# Medium_switch_1.net
KiCad netlist of a schematic drawn in EAGLE
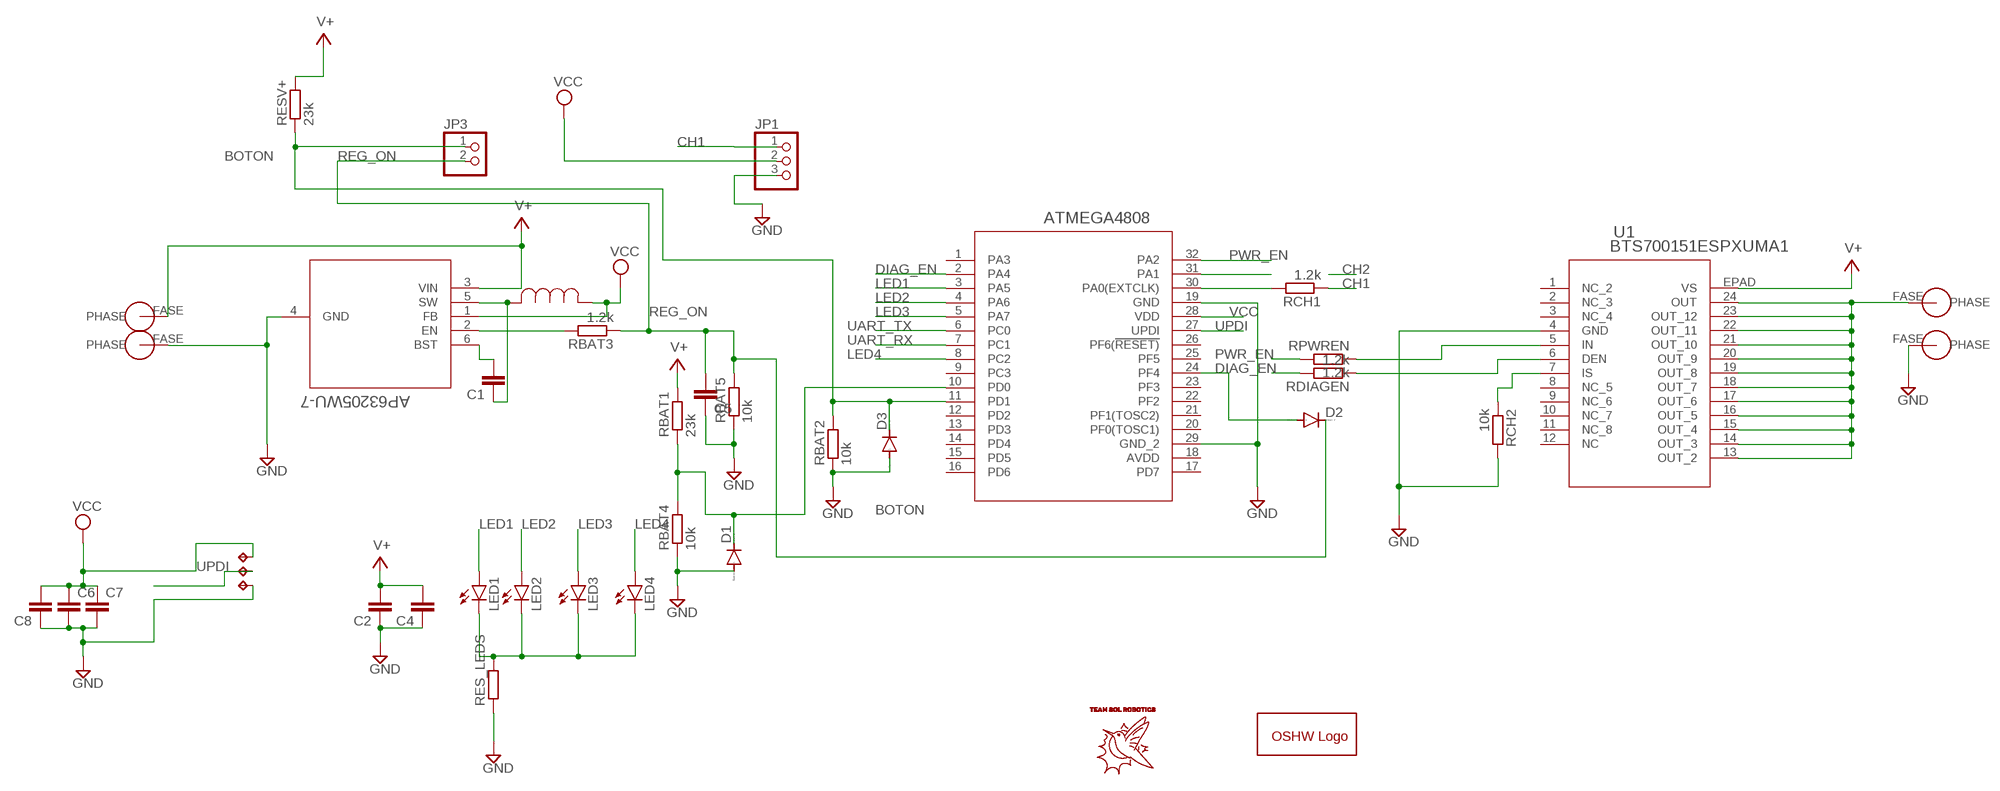
[diagram p0: schematic, sheet 1]

(export (version "E")
  (design (tool "Eeschema 10.0.6"))
  (components
    (comp (ref "BAT+")
      (value "PHASE")
      (footprint "eagle-import:POWEROUT")
      (libsource (lib "eagle-import") (part "PHASE"))
    )
    (comp (ref "C1")
      (value "C-EUC0402")
      (footprint "eagle-import:C0402")
      (libsource (lib "eagle-import") (part "C-EUC0402"))
    )
    (comp (ref "C2")
      (value "C-EUC1206")
      (footprint "eagle-import:C1206")
      (libsource (lib "eagle-import") (part "C-EUC1206"))
    )
    (comp (ref "C4")
      (value "C-EUC1206")
      (footprint "eagle-import:C1206")
      (libsource (lib "eagle-import") (part "C-EUC1206"))
    )
    (comp (ref "C5")
      (value "C-EUC0402")
      (footprint "eagle-import:C0402")
      (libsource (lib "eagle-import") (part "C-EUC0402"))
    )
    (comp (ref "C6")
      (value "C-EUC0805")
      (footprint "eagle-import:C0805")
      (libsource (lib "eagle-import") (part "C-EUC0805"))
    )
    (comp (ref "C7")
      (value "C-EUC0805")
      (footprint "eagle-import:C0805")
      (libsource (lib "eagle-import") (part "C-EUC0805"))
    )
    (comp (ref "C8")
      (value "C-EUC0402")
      (footprint "eagle-import:C0402")
      (libsource (lib "eagle-import") (part "C-EUC0402"))
    )
    (comp (ref "D1")
      (value "DIODE-MICROMELF-R")
      (footprint "eagle-import:MICROMELF-R")
      (libsource (lib "eagle-import") (part "DIODE-MICROMELF-R"))
    )
    (comp (ref "D2")
      (value "DIODE-MINIMELF")
      (footprint "eagle-import:MINIMELF")
      (libsource (lib "eagle-import") (part "DIODE-MINIMELF"))
    )
    (comp (ref "D3")
      (value "DIODE-MICROMELF-R")
      (footprint "eagle-import:MICROMELF-R")
      (libsource (lib "eagle-import") (part "DIODE-MICROMELF-R"))
    )
    (comp (ref "FASEA1")
      (value "PHASE")
      (footprint "eagle-import:POWEROUT")
      (libsource (lib "eagle-import") (part "PHASE"))
    )
    (comp (ref "FASEA3")
      (value "PHASE")
      (footprint "eagle-import:POWEROUT")
      (libsource (lib "eagle-import") (part "PHASE"))
    )
    (comp (ref "GOLD_ORB_SM1")
      (value "OSHWLOGOLOGO5MM")
      (footprint "eagle-import:OSHW_5MM")
      (libsource (lib "eagle-import") (part "OSHWLOGOLOGO5MM"))
    )
    (comp (ref "JP1")
      (value "PINHD-1X03_2.54-S")
      (footprint "eagle-import:1X03-S")
      (libsource (lib "eagle-import") (part "PINHD-1X03_2.54-S"))
    )
    (comp (ref "JP3")
      (value "PINHD-1X02_2.00")
      (footprint "eagle-import:1X02M")
      (libsource (lib "eagle-import") (part "PINHD-1X02_2.00"))
    )
    (comp (ref "LED1")
      (value "LEDSML0603")
      (footprint "eagle-import:SML0603")
      (libsource (lib "eagle-import") (part "LEDSML0603"))
    )
    (comp (ref "LED2")
      (value "LEDSML0603")
      (footprint "eagle-import:SML0603")
      (libsource (lib "eagle-import") (part "LEDSML0603"))
    )
    (comp (ref "LED3")
      (value "LEDSML0603")
      (footprint "eagle-import:SML0603")
      (libsource (lib "eagle-import") (part "LEDSML0603"))
    )
    (comp (ref "LED4")
      (value "LEDSML0603")
      (footprint "eagle-import:SML0603")
      (libsource (lib "eagle-import") (part "LEDSML0603"))
    )
    (comp (ref "OUTPUTPWR")
      (value "PHASE")
      (footprint "eagle-import:POWEROUT")
      (libsource (lib "eagle-import") (part "PHASE"))
    )
    (comp (ref "RBAT1")
      (value "23k")
      (footprint "eagle-import:R0603")
      (libsource (lib "eagle-import") (part "R-EU_R0603"))
    )
    (comp (ref "RBAT2")
      (value "10k")
      (footprint "eagle-import:R0603")
      (libsource (lib "eagle-import") (part "R-EU_R0603"))
    )
    (comp (ref "RBAT3")
      (value "1.2k")
      (footprint "eagle-import:R0603")
      (libsource (lib "eagle-import") (part "R-EU_R0603"))
    )
    (comp (ref "RBAT4")
      (value "10k")
      (footprint "eagle-import:R0603")
      (libsource (lib "eagle-import") (part "R-EU_R0603"))
    )
    (comp (ref "RBAT5")
      (value "10k")
      (footprint "eagle-import:R0603")
      (libsource (lib "eagle-import") (part "R-EU_R0603"))
    )
    (comp (ref "RCH1")
      (value "1.2k")
      (footprint "eagle-import:R0603")
      (libsource (lib "eagle-import") (part "R-EU_R0603"))
    )
    (comp (ref "RCH2")
      (value "10k")
      (footprint "eagle-import:R0603")
      (libsource (lib "eagle-import") (part "R-EU_R0603"))
    )
    (comp (ref "RDIAGEN")
      (value "1.2k")
      (footprint "eagle-import:R0603")
      (libsource (lib "eagle-import") (part "R-EU_R0603"))
    )
    (comp (ref "RESV+")
      (value "23k")
      (footprint "eagle-import:R0603")
      (libsource (lib "eagle-import") (part "R-EU_R0603"))
    )
    (comp (ref "RES_LEDS")
      (value "R-EU_R0603")
      (footprint "eagle-import:R0603")
      (libsource (lib "eagle-import") (part "R-EU_R0603"))
    )
    (comp (ref "RPWREN")
      (value "1.2k")
      (footprint "eagle-import:R0603")
      (libsource (lib "eagle-import") (part "R-EU_R0603"))
    )
    (comp (ref "TP1")
      (value "TPTP13SQ")
      (footprint "eagle-import:TP13SQ")
      (libsource (lib "eagle-import") (part "TPTP13SQ"))
    )
    (comp (ref "TP2")
      (value "TPTP13SQ")
      (footprint "eagle-import:TP13SQ")
      (libsource (lib "eagle-import") (part "TPTP13SQ"))
    )
    (comp (ref "TP3")
      (value "TPTP13SQ")
      (footprint "eagle-import:TP13SQ")
      (libsource (lib "eagle-import") (part "TPTP13SQ"))
    )
    (comp (ref "U$1")
      (value "ATMEGA4808")
      (footprint "eagle-import:QFP80P900X900X120-32N")
      (libsource (lib "eagle-import") (part "ATMEGA4808"))
    )
    (comp (ref "U$3")
      (value "INDUCTOR4.7")
      (footprint "eagle-import:IND_NRS5030T100MMGJ_TAY")
      (libsource (lib "eagle-import") (part "INDUCTOR4.7"))
    )
    (comp (ref "U1")
      (value "BTS700151ESPXUMA1")
      (footprint "eagle-import:PG-TSDSO-24-32")
      (fields (field (name "COPYRIGHT") "Copyright (C) 2023 Ultra Librarian. All rights reserved."))
      (libsource (lib "eagle-import") (part "BTS700151ESPXUMA1"))
    )
    (comp (ref "U2")
      (value "AP63205WU-7")
      (footprint "eagle-import:SOIC_05WU-7_DIO")
      (fields (field (name "COPYRIGHT") "Copyright (C) 2018 Accelerated Designs. All rights reserved"))
      (libsource (lib "eagle-import") (part "AP63205WU-7"))
    )
  )
  (nets
    (net (code "1") (name "/AVDD") (class "Default")
      (node (ref "U$1") (pin "18") (pinfunction "AVDD_18") (pintype "power_in"))
    )
    (net (code "2") (name "/BOTON") (class "Default")
      (node (ref "D3") (pin "C") (pinfunction "C_C") (pintype "passive"))
      (node (ref "JP3") (pin "1") (pinfunction "1_1") (pintype "passive"))
      (node (ref "RBAT2") (pin "2") (pinfunction "2_2") (pintype "passive"))
      (node (ref "RESV+") (pin "1") (pinfunction "1_1") (pintype "passive"))
      (node (ref "U$1") (pin "11") (pinfunction "PD1_11") (pintype "bidirectional"))
    )
    (net (code "3") (name "/CH1") (class "Default")
      (node (ref "JP1") (pin "1") (pinfunction "1_1") (pintype "passive"))
      (node (ref "RCH1") (pin "1") (pinfunction "1_1") (pintype "passive"))
    )
    (net (code "5") (name "/DIAG_EN") (class "Default")
      (node (ref "RDIAGEN") (pin "2") (pinfunction "2_2") (pintype "passive"))
      (node (ref "U$1") (pin "2") (pinfunction "PA4_2") (pintype "bidirectional"))
    )
    (net (code "6") (name "/LED1") (class "Default")
      (node (ref "LED1") (pin "A") (pinfunction "A_A") (pintype "passive"))
      (node (ref "U$1") (pin "3") (pinfunction "PA5_3") (pintype "bidirectional"))
    )
    (net (code "7") (name "/LED2") (class "Default")
      (node (ref "LED2") (pin "A") (pinfunction "A_A") (pintype "passive"))
      (node (ref "U$1") (pin "4") (pinfunction "PA6_4") (pintype "bidirectional"))
    )
    (net (code "8") (name "/LED3") (class "Default")
      (node (ref "LED3") (pin "A") (pinfunction "A_A") (pintype "passive"))
      (node (ref "U$1") (pin "5") (pinfunction "PA7_5") (pintype "bidirectional"))
    )
    (net (code "9") (name "/LED4") (class "Default")
      (node (ref "LED4") (pin "A") (pinfunction "A_A") (pintype "passive"))
      (node (ref "U$1") (pin "8") (pinfunction "PC2_8") (pintype "bidirectional"))
    )
    (net (code "10") (name "/PWR_EN") (class "Default")
      (node (ref "RPWREN") (pin "2") (pinfunction "2_2") (pintype "passive"))
      (node (ref "U$1") (pin "32") (pinfunction "PA2_32") (pintype "bidirectional"))
    )
    (net (code "11") (name "/REG_ON") (class "Default")
      (node (ref "C5") (pin "2") (pinfunction "2_2") (pintype "passive"))
      (node (ref "D2") (pin "C") (pinfunction "C_C") (pintype "passive"))
      (node (ref "JP3") (pin "2") (pinfunction "2_2") (pintype "passive"))
      (node (ref "RBAT3") (pin "1") (pinfunction "1_1") (pintype "passive"))
      (node (ref "RBAT5") (pin "2") (pinfunction "2_2") (pintype "passive"))
    )
    (net (code "12") (name "/UART_RX") (class "Default")
      (node (ref "U$1") (pin "7") (pinfunction "PC1_7") (pintype "bidirectional"))
    )
    (net (code "13") (name "/UART_TX") (class "Default")
      (node (ref "U$1") (pin "6") (pinfunction "PC0_6") (pintype "bidirectional"))
    )
    (net (code "14") (name "/UPDI") (class "Default")
      (node (ref "TP3") (pin "TP") (pinfunction "TP_TP") (pintype "input"))
      (node (ref "U$1") (pin "27") (pinfunction "UPDI_27") (pintype "bidirectional"))
    )
    (net (code "15") (name "GND") (class "Default")
      (node (ref "C2") (pin "1") (pinfunction "1_1") (pintype "passive"))
      (node (ref "C4") (pin "1") (pinfunction "1_1") (pintype "passive"))
      (node (ref "C5") (pin "1") (pinfunction "1_1") (pintype "passive"))
      (node (ref "C6") (pin "2") (pinfunction "2_2") (pintype "passive"))
      (node (ref "C7") (pin "2") (pinfunction "2_2") (pintype "passive"))
      (node (ref "C8") (pin "1") (pinfunction "1_1") (pintype "passive"))
      (node (ref "D1") (pin "A") (pinfunction "A_A") (pintype "passive"))
      (node (ref "D3") (pin "A") (pinfunction "A_A") (pintype "passive"))
      (node (ref "FASEA1") (pin "FASE") (pinfunction "PHASE_FASE") (pintype "bidirectional"))
      (node (ref "FASEA3") (pin "FASE") (pinfunction "PHASE_FASE") (pintype "bidirectional"))
      (node (ref "JP1") (pin "3") (pinfunction "3_3") (pintype "passive"))
      (node (ref "RBAT2") (pin "1") (pinfunction "1_1") (pintype "passive"))
      (node (ref "RBAT4") (pin "1") (pinfunction "1_1") (pintype "passive"))
      (node (ref "RBAT5") (pin "1") (pinfunction "1_1") (pintype "passive"))
      (node (ref "RCH2") (pin "2") (pinfunction "2_2") (pintype "passive"))
      (node (ref "RES_LEDS") (pin "1") (pinfunction "1_1") (pintype "passive"))
      (node (ref "TP2") (pin "TP") (pinfunction "TP_TP") (pintype "input"))
      (node (ref "U$1") (pin "19") (pinfunction "GND_19") (pintype "passive"))
      (node (ref "U$1") (pin "29") (pinfunction "GND_2_29") (pintype "passive"))
      (node (ref "U1") (pin "4") (pinfunction "GND_4") (pintype "passive"))
      (node (ref "U2") (pin "4") (pinfunction "GND_4") (pintype "passive"))
    )
    (net (code "16") (name "Net-(LED1-PadC)") (class "Default")
      (node (ref "LED1") (pin "C") (pinfunction "C_C") (pintype "passive"))
      (node (ref "LED2") (pin "C") (pinfunction "C_C") (pintype "passive"))
      (node (ref "LED3") (pin "C") (pinfunction "C_C") (pintype "passive"))
      (node (ref "LED4") (pin "C") (pinfunction "C_C") (pintype "passive"))
      (node (ref "RES_LEDS") (pin "2") (pinfunction "2_2") (pintype "passive"))
    )
    (net (code "17") (name "Net-(OUTPUTPWR-PHASE)") (class "Default")
      (node (ref "OUTPUTPWR") (pin "FASE") (pinfunction "PHASE_FASE") (pintype "bidirectional"))
      (node (ref "U1") (pin "13") (pinfunction "OUT_2_13") (pintype "output"))
      (node (ref "U1") (pin "14") (pinfunction "OUT_3_14") (pintype "output"))
      (node (ref "U1") (pin "15") (pinfunction "OUT_4_15") (pintype "output"))
      (node (ref "U1") (pin "16") (pinfunction "OUT_5_16") (pintype "output"))
      (node (ref "U1") (pin "17") (pinfunction "OUT_6_17") (pintype "output"))
      (node (ref "U1") (pin "18") (pinfunction "OUT_7_18") (pintype "output"))
      (node (ref "U1") (pin "19") (pinfunction "OUT_8_19") (pintype "output"))
      (node (ref "U1") (pin "20") (pinfunction "OUT_9_20") (pintype "output"))
      (node (ref "U1") (pin "21") (pinfunction "OUT_10_21") (pintype "output"))
      (node (ref "U1") (pin "22") (pinfunction "OUT_11_22") (pintype "output"))
      (node (ref "U1") (pin "23") (pinfunction "OUT_12_23") (pintype "output"))
      (node (ref "U1") (pin "24") (pinfunction "OUT_24") (pintype "output"))
    )
    (net (code "18") (name "Net-(U$1-PA0(EXTCLK))") (class "Default")
      (node (ref "RCH1") (pin "2") (pinfunction "2_2") (pintype "passive"))
      (node (ref "U$1") (pin "30") (pinfunction "PA0(EXTCLK)_30") (pintype "bidirectional"))
    )
    (net (code "19") (name "Net-(U$1-PD0)") (class "Default")
      (node (ref "D1") (pin "C") (pinfunction "C_C") (pintype "passive"))
      (node (ref "RBAT1") (pin "1") (pinfunction "1_1") (pintype "passive"))
      (node (ref "RBAT4") (pin "2") (pinfunction "2_2") (pintype "passive"))
      (node (ref "U$1") (pin "10") (pinfunction "PD0_10") (pintype "bidirectional"))
    )
    (net (code "20") (name "Net-(U$1-PF4)") (class "Default")
      (node (ref "D2") (pin "A") (pinfunction "A_A") (pintype "passive"))
      (node (ref "U$1") (pin "24") (pinfunction "PF4_24") (pintype "bidirectional"))
    )
    (net (code "21") (name "Net-(U1-DEN)") (class "Default")
      (node (ref "RDIAGEN") (pin "1") (pinfunction "1_1") (pintype "passive"))
      (node (ref "U1") (pin "6") (pinfunction "DEN_6") (pintype "passive"))
    )
    (net (code "22") (name "Net-(U1-IN)") (class "Default")
      (node (ref "RPWREN") (pin "1") (pinfunction "1_1") (pintype "passive"))
      (node (ref "U1") (pin "5") (pinfunction "IN_5") (pintype "input"))
    )
    (net (code "23") (name "Net-(U1-IS)") (class "Default")
      (node (ref "RCH2") (pin "1") (pinfunction "1_1") (pintype "passive"))
      (node (ref "U1") (pin "7") (pinfunction "IS_7") (pintype "passive"))
    )
    (net (code "24") (name "Net-(U2-BST)") (class "Default")
      (node (ref "C1") (pin "2") (pinfunction "2_2") (pintype "passive"))
      (node (ref "U2") (pin "6") (pinfunction "BST_6") (pintype "passive"))
    )
    (net (code "25") (name "Net-(U2-EN)") (class "Default")
      (node (ref "RBAT3") (pin "2") (pinfunction "2_2") (pintype "passive"))
      (node (ref "U2") (pin "2") (pinfunction "EN_2") (pintype "passive"))
    )
    (net (code "26") (name "Net-(U2-SW)") (class "Default")
      (node (ref "C1") (pin "1") (pinfunction "1_1") (pintype "passive"))
      (node (ref "U$3") (pin "2") (pinfunction "2_2") (pintype "passive"))
      (node (ref "U2") (pin "5") (pinfunction "SW_5") (pintype "passive"))
    )
    (net (code "27") (name "V+") (class "Default")
      (node (ref "BAT+") (pin "FASE") (pinfunction "PHASE_FASE") (pintype "bidirectional"))
      (node (ref "C2") (pin "2") (pinfunction "2_2") (pintype "passive"))
      (node (ref "C4") (pin "2") (pinfunction "2_2") (pintype "passive"))
      (node (ref "RBAT1") (pin "2") (pinfunction "2_2") (pintype "passive"))
      (node (ref "RESV+") (pin "2") (pinfunction "2_2") (pintype "passive"))
      (node (ref "U1") (pin "EPAD") (pinfunction "VS_EPAD") (pintype "passive"))
      (node (ref "U2") (pin "3") (pinfunction "VIN_3") (pintype "passive"))
    )
    (net (code "28") (name "VCC") (class "Default")
      (node (ref "C6") (pin "1") (pinfunction "1_1") (pintype "passive"))
      (node (ref "C7") (pin "1") (pinfunction "1_1") (pintype "passive"))
      (node (ref "C8") (pin "2") (pinfunction "2_2") (pintype "passive"))
      (node (ref "JP1") (pin "2") (pinfunction "2_2") (pintype "passive"))
      (node (ref "TP1") (pin "TP") (pinfunction "TP_TP") (pintype "input"))
      (node (ref "U$1") (pin "28") (pinfunction "VDD_28") (pintype "power_in"))
      (node (ref "U$3") (pin "1") (pinfunction "1_1") (pintype "passive"))
      (node (ref "U2") (pin "1") (pinfunction "FB_1") (pintype "passive"))
    )
    (net (code "29") (name "unconnected-(U$1-PA1-Pad31)") (class "Default")
      (node (ref "U$1") (pin "31") (pinfunction "PA1_31") (pintype "bidirectional"))
    )
    (net (code "30") (name "unconnected-(U$1-PA3-Pad1)") (class "Default")
      (node (ref "U$1") (pin "1") (pinfunction "PA3_1") (pintype "bidirectional"))
    )
    (net (code "31") (name "unconnected-(U$1-PC3-Pad9)") (class "Default")
      (node (ref "U$1") (pin "9") (pinfunction "PC3_9") (pintype "bidirectional"))
    )
    (net (code "32") (name "unconnected-(U$1-PD2-Pad12)") (class "Default")
      (node (ref "U$1") (pin "12") (pinfunction "PD2_12") (pintype "bidirectional"))
    )
    (net (code "33") (name "unconnected-(U$1-PD3-Pad13)") (class "Default")
      (node (ref "U$1") (pin "13") (pinfunction "PD3_13") (pintype "bidirectional"))
    )
    (net (code "34") (name "unconnected-(U$1-PD4-Pad14)") (class "Default")
      (node (ref "U$1") (pin "14") (pinfunction "PD4_14") (pintype "bidirectional"))
    )
    (net (code "35") (name "unconnected-(U$1-PD5-Pad15)") (class "Default")
      (node (ref "U$1") (pin "15") (pinfunction "PD5_15") (pintype "bidirectional"))
    )
    (net (code "36") (name "unconnected-(U$1-PD6-Pad16)") (class "Default")
      (node (ref "U$1") (pin "16") (pinfunction "PD6_16") (pintype "bidirectional"))
    )
    (net (code "37") (name "unconnected-(U$1-PD7-Pad17)") (class "Default")
      (node (ref "U$1") (pin "17") (pinfunction "PD7_17") (pintype "bidirectional"))
    )
    (net (code "38") (name "unconnected-(U$1-PF0(TOSC1)-Pad20)") (class "Default")
      (node (ref "U$1") (pin "20") (pinfunction "PF0(TOSC1)_20") (pintype "bidirectional"))
    )
    (net (code "39") (name "unconnected-(U$1-PF1(TOSC2)-Pad21)") (class "Default")
      (node (ref "U$1") (pin "21") (pinfunction "PF1(TOSC2)_21") (pintype "bidirectional"))
    )
    (net (code "40") (name "unconnected-(U$1-PF2-Pad22)") (class "Default")
      (node (ref "U$1") (pin "22") (pinfunction "PF2_22") (pintype "bidirectional"))
    )
    (net (code "41") (name "unconnected-(U$1-PF3-Pad23)") (class "Default")
      (node (ref "U$1") (pin "23") (pinfunction "PF3_23") (pintype "bidirectional"))
    )
    (net (code "42") (name "unconnected-(U$1-PF5-Pad25)") (class "Default")
      (node (ref "U$1") (pin "25") (pinfunction "PF5_25") (pintype "bidirectional"))
    )
    (net (code "43") (name "unconnected-(U$1-PF6(~{RESET})-Pad26)") (class "Default")
      (node (ref "U$1") (pin "26") (pinfunction "PF6(~{RESET})_26") (pintype "bidirectional"))
    )
    (net (code "44") (name "unconnected-(U1-NC-Pad12)") (class "Default")
      (node (ref "U1") (pin "12") (pinfunction "NC_12") (pintype "no_connect"))
    )
    (net (code "45") (name "unconnected-(U1-NC_2-Pad1)") (class "Default")
      (node (ref "U1") (pin "1") (pinfunction "NC_2_1") (pintype "no_connect"))
    )
    (net (code "46") (name "unconnected-(U1-NC_3-Pad2)") (class "Default")
      (node (ref "U1") (pin "2") (pinfunction "NC_3_2") (pintype "no_connect"))
    )
    (net (code "47") (name "unconnected-(U1-NC_4-Pad3)") (class "Default")
      (node (ref "U1") (pin "3") (pinfunction "NC_4_3") (pintype "no_connect"))
    )
    (net (code "48") (name "unconnected-(U1-NC_5-Pad8)") (class "Default")
      (node (ref "U1") (pin "8") (pinfunction "NC_5_8") (pintype "no_connect"))
    )
    (net (code "49") (name "unconnected-(U1-NC_6-Pad9)") (class "Default")
      (node (ref "U1") (pin "9") (pinfunction "NC_6_9") (pintype "no_connect"))
    )
    (net (code "50") (name "unconnected-(U1-NC_7-Pad10)") (class "Default")
      (node (ref "U1") (pin "10") (pinfunction "NC_7_10") (pintype "no_connect"))
    )
    (net (code "51") (name "unconnected-(U1-NC_8-Pad11)") (class "Default")
      (node (ref "U1") (pin "11") (pinfunction "NC_8_11") (pintype "no_connect"))
    )
  )
)
